# 7_PowerManagement.net
KiCad netlist of a schematic drawn in Altium Designer
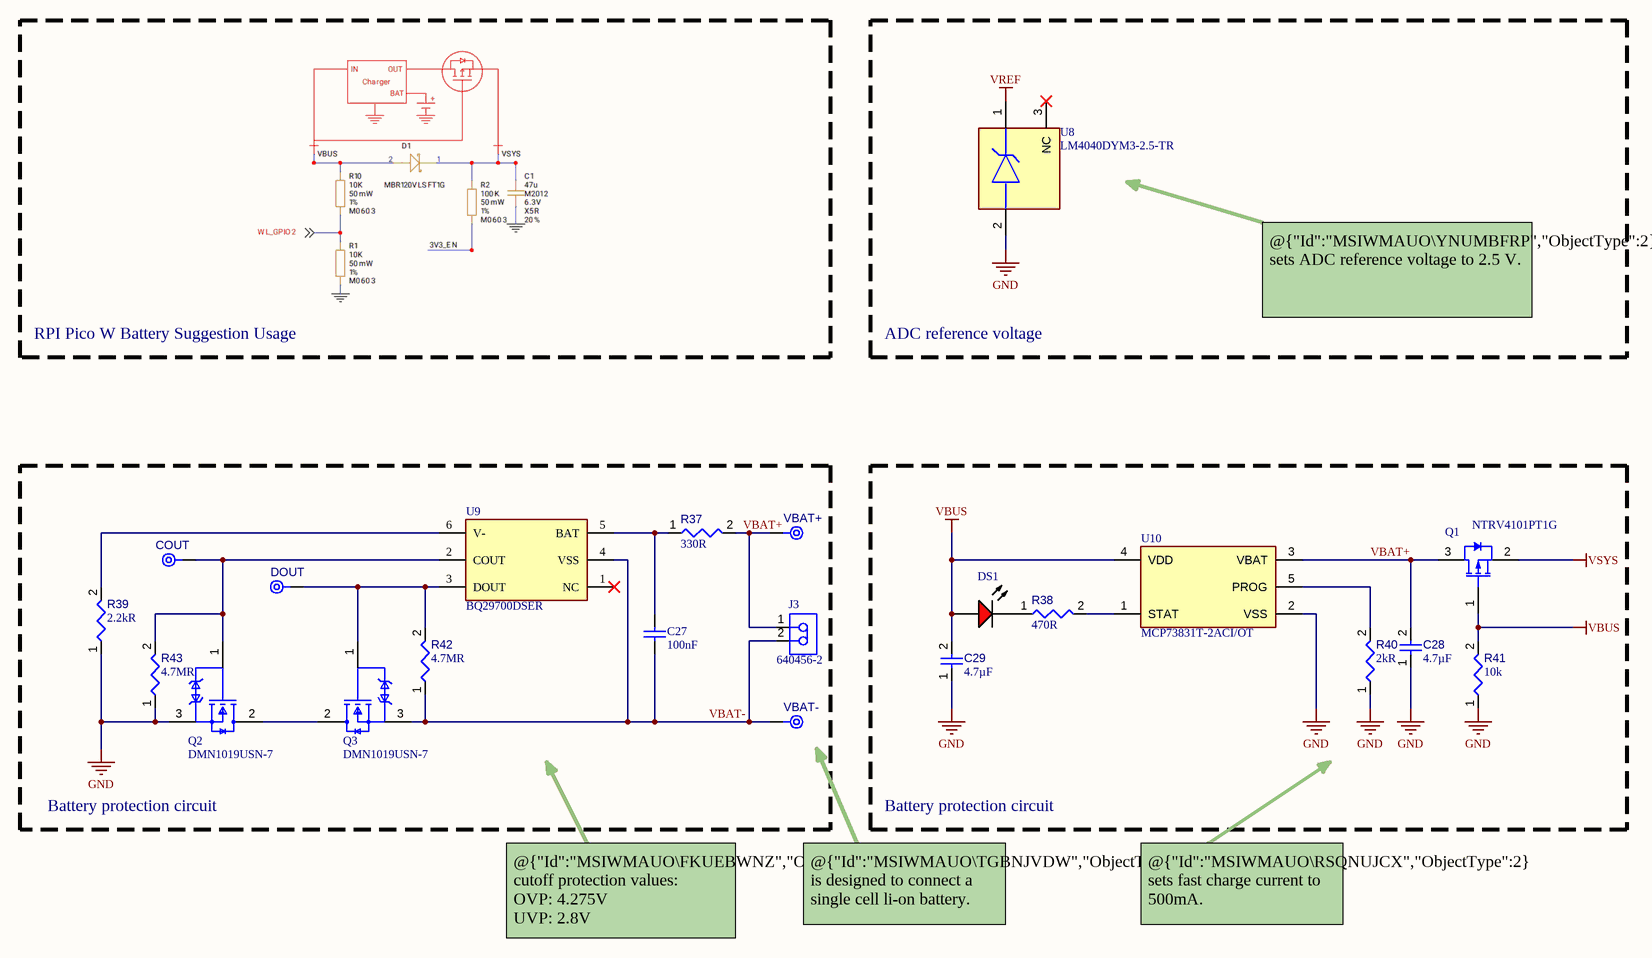
[diagram p0: [7] PowerManagement.SchDoc]

(export (version "E")
  (design (tool "Eeschema 10.0.6"))
  (components
    (comp (ref "C27")
      (value "100nF")
      (footprint "CAPC0603(1608)100_L")
      (description "Multilayer Ceramic Capacitor, 0.1 uF, 16 V, ± 20%, X7R, 0603 [1608 Metric]")
      (fields (field (name "TOLERANCE") "20%") (field (name "Comment") "VJ0603Y104MXJCW1BC"))
      (libsource (lib "UFCG - Universidade Federal de Campina Grande") (part "CAP"))
    )
    (comp (ref "C28")
      (value "4.7µF")
      (footprint "CAPC0603(1608)100_L")
      (description "Chip Capacitor, 4.7µF +/-20%, 10V, 0603, Thickness 1 mm")
      (fields (field (name "TOLERANCE") "10%") (field (name "Comment") "Capacitor 4.7µF +/-20% 10V 0603"))
      (libsource (lib "UFCG - Universidade Federal de Campina Grande") (part "CAP-NP-2"))
    )
    (comp (ref "C29")
      (value "4.7µF")
      (footprint "CAPC0603(1608)100_L")
      (description "Chip Capacitor, 4.7µF +/-20%, 10V, 0603, Thickness 1 mm")
      (fields (field (name "TOLERANCE") "10%") (field (name "Comment") "Capacitor 4.7µF +/-20% 10V 0603"))
      (libsource (lib "UFCG - Universidade Federal de Campina Grande") (part "CAP-NP-2"))
    )
    (comp (ref "COUT")
      (value "TPAD6R")
      (footprint "TP06R")
      (description "0.6mm round")
      (libsource (lib "UFCG - Universidade Federal de Campina Grande") (part "CMP-001-0001-4"))
    )
    (comp (ref "DOUT")
      (value "TPAD6R")
      (footprint "TP06R")
      (description "0.6mm round")
      (libsource (lib "UFCG - Universidade Federal de Campina Grande") (part "CMP-001-0001-4"))
    )
    (comp (ref "DS1")
      (value "19-217/R6C-AL1M2VY/3T")
      (footprint "EVRL-0603-2_V")
      (description "Chip LED, Red, 5 V, 25 mA, -40 to 85 degC, 2-Pin SMD (0603), RoHS, Tape and Reel")
      (fields (field (name "MANUFACTURER") "Everlight Electronics"))
      (libsource (lib "UFCG - Universidade Federal de Campina Grande") (part "LED-RED-AK-2"))
    )
    (comp (ref "J3")
      (value "640456-2")
      (footprint "TECO-640456-2_V")
      (description "Connector 250V AC/DC 5A 2P 1 Row PCB - Vertical Mounting Polyester White")
      (libsource (lib "UFCG - Universidade Federal de Campina Grande") (part "CN-2P-F-QF2"))
    )
    (comp (ref "Q1")
      (value "NTRV4101PT1G")
      (footprint "ONSC-SOT-23-3-318-08_V")
      (description "NTRV4101PT1G P-channel MOSFET Transistor; 1.7 A; 20 V; 3-Pin SOT-23")
      (libsource (lib "UFCG - Universidade Federal de Campina Grande") (part "ONSC-PMOS-G1S2D3-3_D"))
    )
    (comp (ref "Q2")
      (value "DMN1019USN-7")
      (footprint "FP-SC59-MFG")
      (description "N-Channel 12 V 10 mO 50.6 nC SMT Enhancement Mode Mosfet - SC-59 (SOT-23)")
      (libsource (lib "UFCG - Universidade Federal de Campina Grande") (part "587d6cfc489599008faafaa59ebe43c"))
    )
    (comp (ref "Q3")
      (value "DMN1019USN-7")
      (footprint "FP-SC59-MFG")
      (description "N-Channel 12 V 10 mO 50.6 nC SMT Enhancement Mode Mosfet - SC-59 (SOT-23)")
      (libsource (lib "UFCG - Universidade Federal de Campina Grande") (part "587d6cfc489599008faafaa59ebe43c"))
    )
    (comp (ref "R37")
      (value "330R")
      (footprint "RESC0603(1608)_L")
      (description "SMD Chip Resistor, 330 Ohm, ± 1%, 100 mW, 0603 [1608 Metric], Thick Film, Precision")
      (fields (field (name "TOLERANCE") "1%") (field (name "Comment") "ERJ-3EKF3300V"))
      (libsource (lib "UFCG - Universidade Federal de Campina Grande") (part "RES-2"))
    )
    (comp (ref "R38")
      (value "470R")
      (footprint "RESC0603(1608)_L")
      (description "Res Thick Film 0603 470 Ohm 5% 0.1W(1/10W) ±200ppm/°C Pad SMD Automotive T/R")
      (fields (field (name "TOLERANCE") "5%") (field (name "Comment") "CRCW0603470RJNEA"))
      (libsource (lib "UFCG - Universidade Federal de Campina Grande") (part "RES-2"))
    )
    (comp (ref "R39")
      (value "2.2kR")
      (footprint "RESC0603(1608)_L")
      (description "SMD Chip Resistor, 2.2 kOhm, ± 1%, 100 mW, 0603 [1608 Metric], Thick Film, General Purpose")
      (fields (field (name "TOLERANCE") "1%") (field (name "Comment") "CRCW06032K20FKEA"))
      (libsource (lib "UFCG - Universidade Federal de Campina Grande") (part "RES-2"))
    )
    (comp (ref "R40")
      (value "2kR")
      (footprint "RESC0603(1608)_L")
      (description "SMD Chip Resistor, 2 kOhm, ï¿½ 1%, 100 mW, 0603 [1608 Metric], Thick Film, Precision")
      (fields (field (name "TOLERANCE") "1%") (field (name "Comment") "ERJ-3EKF2001V"))
      (libsource (lib "UFCG - Universidade Federal de Campina Grande") (part "RES-2"))
    )
    (comp (ref "R41")
      (value "10k")
      (footprint "RESC0603(1608)_L")
      (description "Chip Resistor, 10 KOhm, +/- 1%, 01 W, -55 to 155 degC, 0603 (1608 Metric)")
      (fields (field (name "POWER") "100mW") (field (name "TOLERANCE") "1%"))
      (libsource (lib "UFCG - Universidade Federal de Campina Grande") (part "RES-2"))
    )
    (comp (ref "R42")
      (value "4.7MR")
      (footprint "RESC0603(1608)_L")
      (description "Res Thick Film 0603 4.7M Ohm 5% 0.1W -400ppm/°C to 150ppm/°C Molded SMD Punched Carrier T/R")
      (fields (field (name "TOLERANCE") "5%") (field (name "Comment") "ERJ-3GEYJ475V"))
      (libsource (lib "UFCG - Universidade Federal de Campina Grande") (part "RES-2"))
    )
    (comp (ref "R43")
      (value "4.7MR")
      (footprint "RESC0603(1608)_L")
      (description "Res Thick Film 0603 4.7M Ohm 5% 0.1W -400ppm/°C to 150ppm/°C Molded SMD Punched Carrier T/R")
      (fields (field (name "TOLERANCE") "5%") (field (name "Comment") "ERJ-3GEYJ475V"))
      (libsource (lib "UFCG - Universidade Federal de Campina Grande") (part "RES-2"))
    )
    (comp (ref "U8")
      (value "LM4040DYM3-2.5-TR")
      (footprint "FP-SOT23-3LD-PL-1-IPC_A")
      (description "LM4040 Series 2.5 V ±1 % Precision Micropower Shunt Voltage Reference - SOT-23")
      (fields (field (name "TOLERANCE") "1%"))
      (libsource (lib "UFCG - Universidade Federal de Campina Grande") (part "91f0ca7be5727739b22823fb575e884"))
    )
    (comp (ref "U9")
      (value "BQ29700DSER")
      (footprint "FP-DSE0006A-MFG")
      (description "Li-Ion/Li Polymer Advanced Single-Cell Battery Protector IC Family 6-WSON -40 to 85")
      (libsource (lib "UFCG - Universidade Federal de Campina Grande") (part "cb1a035e2e9bf15fad579f9d3aca51e"))
    )
    (comp (ref "U10")
      (value "MCP73831T-2ACI/OT")
      (footprint "FP-C04-091-OT-MFG")
      (description "MCP73831 Series Single-Cell Li-Ion/Li-Polymer Battery Charge Controller SOT-23-5")
      (libsource (lib "UFCG - Universidade Federal de Campina Grande") (part "61f5a3bb3429d9e0caadea342aa3b19"))
    )
    (comp (ref "VBAT+")
      (value "TPAD6R")
      (footprint "TP06R")
      (description "0.6mm round")
      (libsource (lib "UFCG - Universidade Federal de Campina Grande") (part "CMP-001-0001-4"))
    )
    (comp (ref "VBAT-")
      (value "TPAD6R")
      (footprint "TP06R")
      (description "0.6mm round")
      (libsource (lib "UFCG - Universidade Federal de Campina Grande") (part "CMP-001-0001-4"))
    )
  )
  (nets
    (net (code "1") (name "/VBAT+") (class "Default")
      (node (ref "C28") (pin "2") (pinfunction "2_2") (pintype "passive"))
      (node (ref "J3") (pin "1") (pinfunction "1_1") (pintype "passive"))
      (node (ref "Q1") (pin "3") (pinfunction "D_3") (pintype "passive"))
      (node (ref "R37") (pin "2") (pinfunction "2_2") (pintype "passive"))
      (node (ref "U10") (pin "3") (pinfunction "VBAT_3") (pintype "power_in"))
      (node (ref "VBAT+") (pin "1") (pinfunction "TP_1") (pintype "passive"))
    )
    (net (code "2") (name "/VBAT-") (class "Default")
      (node (ref "C27") (pin "1") (pinfunction "1_1") (pintype "passive"))
      (node (ref "J3") (pin "2") (pinfunction "2_2") (pintype "passive"))
      (node (ref "Q3") (pin "3") (pinfunction "D_3") (pintype "passive"))
      (node (ref "R42") (pin "1") (pinfunction "1_1") (pintype "passive"))
      (node (ref "U9") (pin "4") (pinfunction "VSS_4") (pintype "power_in"))
      (node (ref "VBAT-") (pin "1") (pinfunction "TP_1") (pintype "passive"))
    )
    (net (code "3") (name "GND") (class "Default")
      (node (ref "C28") (pin "1") (pinfunction "1_1") (pintype "passive"))
      (node (ref "C29") (pin "1") (pinfunction "1_1") (pintype "passive"))
      (node (ref "Q2") (pin "3") (pinfunction "D_3") (pintype "passive"))
      (node (ref "R39") (pin "1") (pinfunction "1_1") (pintype "passive"))
      (node (ref "R40") (pin "1") (pinfunction "1_1") (pintype "passive"))
      (node (ref "R41") (pin "1") (pinfunction "1_1") (pintype "passive"))
      (node (ref "R43") (pin "1") (pinfunction "1_1") (pintype "passive"))
      (node (ref "U10") (pin "2") (pinfunction "VSS_2") (pintype "power_in"))
      (node (ref "U8") (pin "2") (pinfunction "-_2") (pintype "passive"))
    )
    (net (code "4") (name "Net-(COUT-TP)") (class "Default")
      (node (ref "COUT") (pin "1") (pinfunction "TP_1") (pintype "passive"))
      (node (ref "Q2") (pin "1") (pinfunction "G_1") (pintype "passive"))
      (node (ref "R43") (pin "2") (pinfunction "2_2") (pintype "passive"))
      (node (ref "U9") (pin "2") (pinfunction "COUT_2") (pintype "passive"))
    )
    (net (code "5") (name "Net-(DOUT-TP)") (class "Default")
      (node (ref "DOUT") (pin "1") (pinfunction "TP_1") (pintype "passive"))
      (node (ref "Q3") (pin "1") (pinfunction "G_1") (pintype "passive"))
      (node (ref "R42") (pin "2") (pinfunction "2_2") (pintype "passive"))
      (node (ref "U9") (pin "3") (pinfunction "DOUT_3") (pintype "passive"))
    )
    (net (code "6") (name "Net-(DS1-K)") (class "Default")
      (node (ref "DS1") (pin "2") (pinfunction "K_2") (pintype "passive"))
      (node (ref "R38") (pin "1") (pinfunction "1_1") (pintype "passive"))
    )
    (net (code "7") (name "Net-(Q2-S)") (class "Default")
      (node (ref "Q2") (pin "2") (pinfunction "S_2") (pintype "passive"))
      (node (ref "Q3") (pin "2") (pinfunction "S_2") (pintype "passive"))
    )
    (net (code "8") (name "Net-(U9-BAT)") (class "Default")
      (node (ref "C27") (pin "2") (pinfunction "2_2") (pintype "passive"))
      (node (ref "R37") (pin "1") (pinfunction "1_1") (pintype "passive"))
      (node (ref "U9") (pin "5") (pinfunction "BAT_5") (pintype "power_in"))
    )
    (net (code "9") (name "Net-(U9-V-)") (class "Default")
      (node (ref "R39") (pin "2") (pinfunction "2_2") (pintype "passive"))
      (node (ref "U9") (pin "6") (pinfunction "V-_6") (pintype "passive"))
    )
    (net (code "10") (name "Net-(U10-PROG)") (class "Default")
      (node (ref "R40") (pin "2") (pinfunction "2_2") (pintype "passive"))
      (node (ref "U10") (pin "5") (pinfunction "PROG_5") (pintype "passive"))
    )
    (net (code "11") (name "Net-(U10-STAT)") (class "Default")
      (node (ref "R38") (pin "2") (pinfunction "2_2") (pintype "passive"))
      (node (ref "U10") (pin "1") (pinfunction "STAT_1") (pintype "passive"))
    )
    (net (code "12") (name "VBUS") (class "Default")
      (node (ref "C29") (pin "2") (pinfunction "2_2") (pintype "passive"))
      (node (ref "DS1") (pin "1") (pinfunction "A_1") (pintype "passive"))
      (node (ref "Q1") (pin "1") (pinfunction "G_1") (pintype "passive"))
      (node (ref "R41") (pin "2") (pinfunction "2_2") (pintype "passive"))
      (node (ref "U10") (pin "4") (pinfunction "VDD_4") (pintype "power_in"))
    )
    (net (code "13") (name "VREF") (class "Default")
      (node (ref "U8") (pin "1") (pinfunction "+_1") (pintype "passive"))
    )
    (net (code "14") (name "VSYS") (class "Default")
      (node (ref "Q1") (pin "2") (pinfunction "S_2") (pintype "passive"))
    )
    (net (code "15") (name "unconnected-(U8-NC-Pad3)") (class "Default")
      (node (ref "U8") (pin "3") (pinfunction "NC_3") (pintype "passive+no_connect"))
    )
    (net (code "16") (name "unconnected-(U9-NC-Pad1)") (class "Default")
      (node (ref "U9") (pin "1") (pinfunction "NC_1") (pintype "passive+no_connect"))
    )
  )
)
